# KGGR_M2_MOS.net
KiCad netlist of a schematic drawn in EAGLE
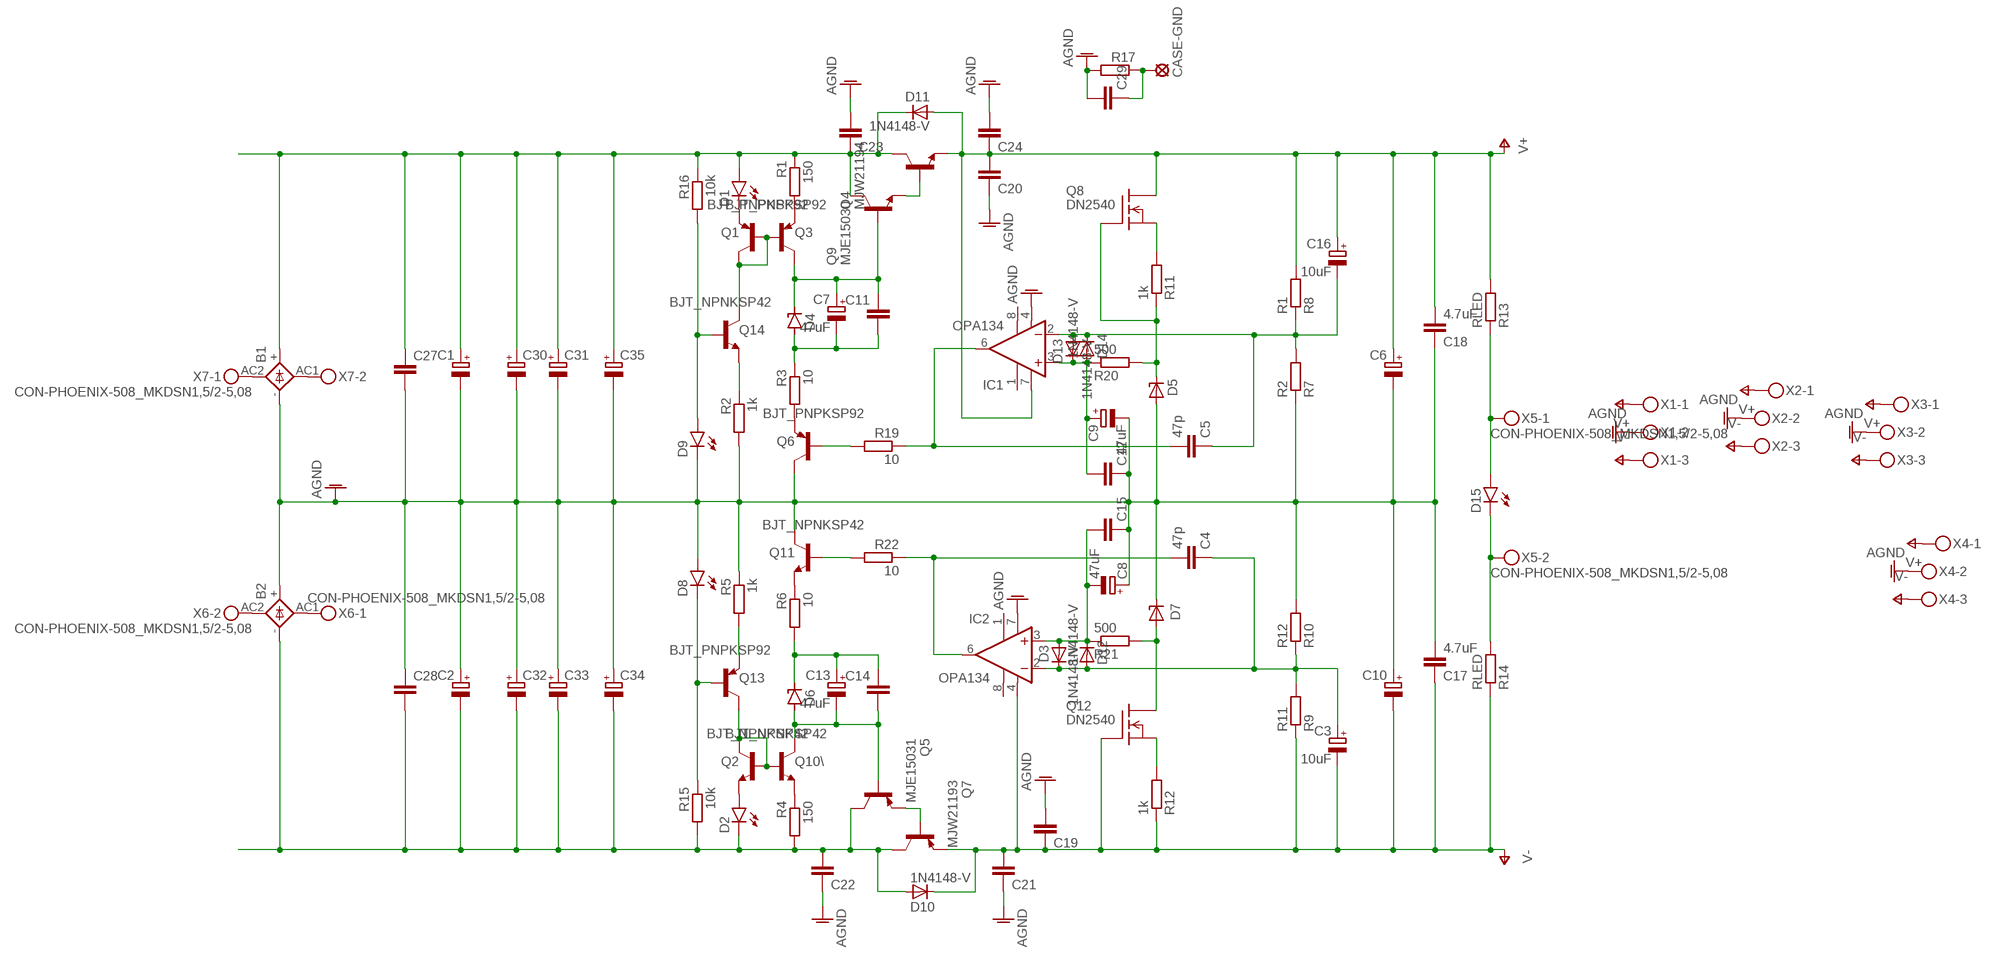
[diagram p0: schematic, sheet 1]

(export (version "E")
  (design (tool "Eeschema 10.0.6"))
  (components
    (comp (ref "B1")
      (value "GBU4")
      (footprint "eagle-import:GBU4S")
      (libsource (lib "eagle-import") (part "GBU4"))
    )
    (comp (ref "B2")
      (value "GBU4")
      (footprint "eagle-import:GBU4S")
      (libsource (lib "eagle-import") (part "GBU4"))
    )
    (comp (ref "C1")
      (value "CPOL-EUE10-35")
      (footprint "eagle-import:EB35D")
      (libsource (lib "eagle-import") (part "CPOL-EUE10-35"))
    )
    (comp (ref "C2")
      (value "CPOL-EUE10-35")
      (footprint "eagle-import:EB35D")
      (libsource (lib "eagle-import") (part "CPOL-EUE10-35"))
    )
    (comp (ref "C3")
      (value "10uF")
      (footprint "eagle-import:E5-8,5")
      (libsource (lib "eagle-import") (part "CPOL-EUE5-8.5"))
    )
    (comp (ref "C4")
      (value "47p")
      (footprint "eagle-import:C025_050-025X075")
      (libsource (lib "eagle-import") (part "C-EU025_050-025X075"))
    )
    (comp (ref "C5")
      (value "47p")
      (footprint "eagle-import:C025_050-025X075")
      (libsource (lib "eagle-import") (part "C-EU025_050-025X075"))
    )
    (comp (ref "C6")
      (value "CPOL-EUE7.5-18")
      (footprint "eagle-import:E7,5-18")
      (libsource (lib "eagle-import") (part "CPOL-EUE7.5-18"))
    )
    (comp (ref "C7")
      (value "47uF")
      (footprint "eagle-import:E5-8,5")
      (libsource (lib "eagle-import") (part "CPOL-EUE5-8.5"))
    )
    (comp (ref "C8")
      (value "47uF")
      (footprint "eagle-import:E5-8,5")
      (libsource (lib "eagle-import") (part "CPOL-EUE5-8.5"))
    )
    (comp (ref "C9")
      (value "47uF")
      (footprint "eagle-import:E5-8,5")
      (libsource (lib "eagle-import") (part "CPOL-EUE5-8.5"))
    )
    (comp (ref "C10")
      (value "CPOL-EUE7.5-18")
      (footprint "eagle-import:E7,5-18")
      (libsource (lib "eagle-import") (part "CPOL-EUE7.5-18"))
    )
    (comp (ref "C11")
      (value "C-EU050-035X075")
      (footprint "eagle-import:C050-035X075")
      (libsource (lib "eagle-import") (part "C-EU050-035X075"))
    )
    (comp (ref "C12")
      (value "C-EU050-035X075")
      (footprint "eagle-import:C050-035X075")
      (libsource (lib "eagle-import") (part "C-EU050-035X075"))
    )
    (comp (ref "C13")
      (value "47uF")
      (footprint "eagle-import:E5-8,5")
      (libsource (lib "eagle-import") (part "CPOL-EUE5-8.5"))
    )
    (comp (ref "C14")
      (value "C-EU050-035X075")
      (footprint "eagle-import:C050-035X075")
      (libsource (lib "eagle-import") (part "C-EU050-035X075"))
    )
    (comp (ref "C15")
      (value "C-EU050-035X075")
      (footprint "eagle-import:C050-035X075")
      (libsource (lib "eagle-import") (part "C-EU050-035X075"))
    )
    (comp (ref "C16")
      (value "10uF")
      (footprint "eagle-import:E5-8,5")
      (libsource (lib "eagle-import") (part "CPOL-EUE5-8.5"))
    )
    (comp (ref "C17")
      (value "4.7uF")
      (footprint "eagle-import:C050-075X075")
      (libsource (lib "eagle-import") (part "C-EU050-075X075"))
    )
    (comp (ref "C18")
      (value "4.7uF")
      (footprint "eagle-import:C050-075X075")
      (libsource (lib "eagle-import") (part "C-EU050-075X075"))
    )
    (comp (ref "C19")
      (value "C-EU050-035X075")
      (footprint "eagle-import:C050-035X075")
      (libsource (lib "eagle-import") (part "C-EU050-035X075"))
    )
    (comp (ref "C20")
      (value "C-EU050-035X075")
      (footprint "eagle-import:C050-035X075")
      (libsource (lib "eagle-import") (part "C-EU050-035X075"))
    )
    (comp (ref "C21")
      (value "C-EU050-035X075")
      (footprint "eagle-import:C050-035X075")
      (libsource (lib "eagle-import") (part "C-EU050-035X075"))
    )
    (comp (ref "C22")
      (value "C-EU050-075X075")
      (footprint "eagle-import:C050-075X075")
      (libsource (lib "eagle-import") (part "C-EU050-075X075"))
    )
    (comp (ref "C23")
      (value "C-EU050-075X075")
      (footprint "eagle-import:C050-075X075")
      (libsource (lib "eagle-import") (part "C-EU050-075X075"))
    )
    (comp (ref "C24")
      (value "C-EU050-035X075")
      (footprint "eagle-import:C050-035X075")
      (libsource (lib "eagle-import") (part "C-EU050-035X075"))
    )
    (comp (ref "C27")
      (value "C-EU102_152-062X184")
      (footprint "eagle-import:C102_152-062X184")
      (libsource (lib "eagle-import") (part "C-EU102_152-062X184"))
    )
    (comp (ref "C28")
      (value "C-EU102_152-062X184")
      (footprint "eagle-import:C102_152-062X184")
      (libsource (lib "eagle-import") (part "C-EU102_152-062X184"))
    )
    (comp (ref "C29")
      (value "C-EU102_152-062X184")
      (footprint "eagle-import:C102_152-062X184")
      (libsource (lib "eagle-import") (part "C-EU102_152-062X184"))
    )
    (comp (ref "C30")
      (value "CPOL-EUE7.5-18")
      (footprint "eagle-import:E7,5-18")
      (libsource (lib "eagle-import") (part "CPOL-EUE7.5-18"))
    )
    (comp (ref "C31")
      (value "CPOL-EUE7.5-18")
      (footprint "eagle-import:E7,5-18")
      (libsource (lib "eagle-import") (part "CPOL-EUE7.5-18"))
    )
    (comp (ref "C32")
      (value "CPOL-EUE7.5-18")
      (footprint "eagle-import:E7,5-18")
      (libsource (lib "eagle-import") (part "CPOL-EUE7.5-18"))
    )
    (comp (ref "C33")
      (value "CPOL-EUE7.5-18")
      (footprint "eagle-import:E7,5-18")
      (libsource (lib "eagle-import") (part "CPOL-EUE7.5-18"))
    )
    (comp (ref "C34")
      (value "CPOL-EUE7.5-18")
      (footprint "eagle-import:E7,5-18")
      (libsource (lib "eagle-import") (part "CPOL-EUE7.5-18"))
    )
    (comp (ref "C35")
      (value "CPOL-EUE7.5-18")
      (footprint "eagle-import:E7,5-18")
      (libsource (lib "eagle-import") (part "CPOL-EUE7.5-18"))
    )
    (comp (ref "CASE-GND")
      (value "SE14")
      (footprint "eagle-import:SE14")
      (libsource (lib "eagle-import") (part "SE14"))
    )
    (comp (ref "D1")
      (value "LED5MM")
      (footprint "eagle-import:LED5MM")
      (libsource (lib "eagle-import") (part "LED5MM"))
    )
    (comp (ref "D2")
      (value "LED5MM")
      (footprint "eagle-import:LED5MM")
      (libsource (lib "eagle-import") (part "LED5MM"))
    )
    (comp (ref "D3")
      (value "1N4148-V")
      (footprint "eagle-import:1N4148")
      (libsource (lib "eagle-import") (part "1N4148-V"))
    )
    (comp (ref "D4")
      (value "1N4728")
      (footprint "eagle-import:DO41Z10")
      (libsource (lib "eagle-import") (part "1N4728"))
    )
    (comp (ref "D5")
      (value "LT1021")
      (footprint "eagle-import:DIL08")
      (libsource (lib "eagle-import") (part "LT1021-V"))
    )
    (comp (ref "D6")
      (value "1N4728")
      (footprint "eagle-import:DO41Z10")
      (libsource (lib "eagle-import") (part "1N4728"))
    )
    (comp (ref "D7")
      (value "LT1021")
      (footprint "eagle-import:DIL08")
      (libsource (lib "eagle-import") (part "LT1021-V"))
    )
    (comp (ref "D8")
      (value "LED5MM")
      (footprint "eagle-import:LED5MM")
      (libsource (lib "eagle-import") (part "LED5MM"))
    )
    (comp (ref "D9")
      (value "LED5MM")
      (footprint "eagle-import:LED5MM")
      (libsource (lib "eagle-import") (part "LED5MM"))
    )
    (comp (ref "D10")
      (value "1N4148-V")
      (footprint "eagle-import:1N4148")
      (libsource (lib "eagle-import") (part "1N4148-V"))
    )
    (comp (ref "D11")
      (value "1N4148-V")
      (footprint "eagle-import:1N4148")
      (libsource (lib "eagle-import") (part "1N4148-V"))
    )
    (comp (ref "D12")
      (value "1N4148-V")
      (footprint "eagle-import:1N4148")
      (libsource (lib "eagle-import") (part "1N4148-V"))
    )
    (comp (ref "D13")
      (value "1N4148-V")
      (footprint "eagle-import:1N4148")
      (libsource (lib "eagle-import") (part "1N4148-V"))
    )
    (comp (ref "D14")
      (value "1N4148-V")
      (footprint "eagle-import:1N4148")
      (libsource (lib "eagle-import") (part "1N4148-V"))
    )
    (comp (ref "D15")
      (value "LED5MM")
      (footprint "eagle-import:LED5MM")
      (libsource (lib "eagle-import") (part "LED5MM"))
    )
    (comp (ref "IC1")
      (value "OPA134")
      (footprint "eagle-import:DIL08")
      (fields (field (name "MF") "TEXAS INSTRUMENTS") (field (name "MPN") "OPA134PA"))
      (libsource (lib "eagle-import") (part "OPA134P"))
    )
    (comp (ref "IC2")
      (value "OPA134")
      (footprint "eagle-import:DIL08")
      (fields (field (name "MF") "TEXAS INSTRUMENTS") (field (name "MPN") "OPA134PA"))
      (libsource (lib "eagle-import") (part "OPA134P"))
    )
    (comp (ref "Q1")
      (value "BJT_PNPKSP92")
      (footprint "eagle-import:TRANSISTOR_TO92-EBC_P")
      (libsource (lib "eagle-import") (part "BJT_PNPKSP92"))
    )
    (comp (ref "Q2")
      (value "BJT_NPNKSP42")
      (footprint "eagle-import:TRANSISTOR_TO92-EBC_N")
      (libsource (lib "eagle-import") (part "BJT_NPNKSP42"))
    )
    (comp (ref "Q3")
      (value "BJT_PNPKSP92")
      (footprint "eagle-import:TRANSISTOR_TO92-EBC_P")
      (libsource (lib "eagle-import") (part "BJT_PNPKSP92"))
    )
    (comp (ref "Q4")
      (value "MJW21194")
      (footprint "eagle-import:TRANSISTOR_TO247_BCE_N")
      (libsource (lib "eagle-import") (part "BJT_NPNMJL4281"))
    )
    (comp (ref "Q5")
      (value "MJE15031")
      (footprint "eagle-import:TO220KG")
      (libsource (lib "eagle-import") (part "MJE15031"))
    )
    (comp (ref "Q6")
      (value "BJT_PNPKSP92")
      (footprint "eagle-import:TRANSISTOR_TO92-EBC_P")
      (libsource (lib "eagle-import") (part "BJT_PNPKSP92"))
    )
    (comp (ref "Q7")
      (value "MJW21193")
      (footprint "eagle-import:TRANSISTOR_TO247_BCE_P")
      (libsource (lib "eagle-import") (part "BJT_PNPMJL4302"))
    )
    (comp (ref "Q8")
      (value "DN2540")
      (footprint "eagle-import:TO92-")
      (libsource (lib "eagle-import") (part "2N7000"))
    )
    (comp (ref "Q9")
      (value "MJE15030")
      (footprint "eagle-import:TO220KG")
      (libsource (lib "eagle-import") (part "MJE15030"))
    )
    (comp (ref "Q10\\")
      (value "BJT_NPNKSP42")
      (footprint "eagle-import:TRANSISTOR_TO92-EBC_N")
      (libsource (lib "eagle-import") (part "BJT_NPNKSP42"))
    )
    (comp (ref "Q11")
      (value "BJT_NPNKSP42")
      (footprint "eagle-import:TRANSISTOR_TO92-EBC_N")
      (libsource (lib "eagle-import") (part "BJT_NPNKSP42"))
    )
    (comp (ref "Q12")
      (value "DN2540")
      (footprint "eagle-import:TO92-")
      (libsource (lib "eagle-import") (part "2N7000"))
    )
    (comp (ref "Q13")
      (value "BJT_PNPKSP92")
      (footprint "eagle-import:TRANSISTOR_TO92-EBC_P")
      (libsource (lib "eagle-import") (part "BJT_PNPKSP92"))
    )
    (comp (ref "Q14")
      (value "BJT_NPNKSP42")
      (footprint "eagle-import:TRANSISTOR_TO92-EBC_N")
      (libsource (lib "eagle-import") (part "BJT_NPNKSP42"))
    )
    (comp (ref "R1")
      (value "150")
      (footprint "eagle-import:0309_12")
      (libsource (lib "eagle-import") (part "R-EU_0309/12"))
    )
    (comp (ref "R2")
      (value "1k")
      (footprint "eagle-import:0309_12")
      (libsource (lib "eagle-import") (part "R-EU_0309/12"))
    )
    (comp (ref "R3")
      (value "10")
      (footprint "eagle-import:0309_12")
      (libsource (lib "eagle-import") (part "R-EU_0309/12"))
    )
    (comp (ref "R4")
      (value "150")
      (footprint "eagle-import:0309_12")
      (libsource (lib "eagle-import") (part "R-EU_0309/12"))
    )
    (comp (ref "R5")
      (value "1k")
      (footprint "eagle-import:0309_12")
      (libsource (lib "eagle-import") (part "R-EU_0309/12"))
    )
    (comp (ref "R6")
      (value "10")
      (footprint "eagle-import:0309_12")
      (libsource (lib "eagle-import") (part "R-EU_0309/12"))
    )
    (comp (ref "R7")
      (value "R2")
      (footprint "eagle-import:0309_12")
      (libsource (lib "eagle-import") (part "R-EU_0309/12"))
    )
    (comp (ref "R8")
      (value "R1")
      (footprint "eagle-import:0309_12")
      (libsource (lib "eagle-import") (part "R-EU_0309/12"))
    )
    (comp (ref "R9")
      (value "R11")
      (footprint "eagle-import:0309_12")
      (libsource (lib "eagle-import") (part "R-EU_0309/12"))
    )
    (comp (ref "R10")
      (value "R12")
      (footprint "eagle-import:0309_12")
      (libsource (lib "eagle-import") (part "R-EU_0309/12"))
    )
    (comp (ref "R11")
      (value "1k")
      (footprint "eagle-import:0309_12")
      (libsource (lib "eagle-import") (part "R-EU_0309/12"))
    )
    (comp (ref "R12")
      (value "1k")
      (footprint "eagle-import:0309_12")
      (libsource (lib "eagle-import") (part "R-EU_0309/12"))
    )
    (comp (ref "R13")
      (value "RLED")
      (footprint "eagle-import:0309_12")
      (libsource (lib "eagle-import") (part "R-EU_0309/12"))
    )
    (comp (ref "R14")
      (value "RLED")
      (footprint "eagle-import:0309_12")
      (libsource (lib "eagle-import") (part "R-EU_0309/12"))
    )
    (comp (ref "R15")
      (value "10k")
      (footprint "eagle-import:0309_12")
      (libsource (lib "eagle-import") (part "R-EU_0309/12"))
    )
    (comp (ref "R16")
      (value "10k")
      (footprint "eagle-import:0309_12")
      (libsource (lib "eagle-import") (part "R-EU_0309/12"))
    )
    (comp (ref "R17")
      (value "R-EU_0617/22")
      (footprint "eagle-import:0617_22")
      (libsource (lib "eagle-import") (part "R-EU_0617/22"))
    )
    (comp (ref "R19")
      (value "10")
      (footprint "eagle-import:0309_12")
      (libsource (lib "eagle-import") (part "R-EU_0309/12"))
    )
    (comp (ref "R20")
      (value "500")
      (footprint "eagle-import:0309_12")
      (libsource (lib "eagle-import") (part "R-EU_0309/12"))
    )
    (comp (ref "R21")
      (value "500")
      (footprint "eagle-import:0309_12")
      (libsource (lib "eagle-import") (part "R-EU_0309/12"))
    )
    (comp (ref "R22")
      (value "10")
      (footprint "eagle-import:0309_12")
      (libsource (lib "eagle-import") (part "R-EU_0309/12"))
    )
    (comp (ref "X1")
      (value "CON-PHOENIX-508_MKDSN1,5/3-5,08")
      (footprint "eagle-import:CON-PHOENIX-508_MKDSN1,5_3-5,08")
      (libsource (lib "eagle-import") (part "CON-PHOENIX-508_MKDSN1,5/3-5,08"))
    )
    (comp (ref "X2")
      (value "CON-PHOENIX-508_MKDSN1,5/3-5,08")
      (footprint "eagle-import:CON-PHOENIX-508_MKDSN1,5_3-5,08")
      (libsource (lib "eagle-import") (part "CON-PHOENIX-508_MKDSN1,5/3-5,08"))
    )
    (comp (ref "X3")
      (value "CON-PHOENIX-508_MKDSN1,5/3-5,08")
      (footprint "eagle-import:CON-PHOENIX-508_MKDSN1,5_3-5,08")
      (libsource (lib "eagle-import") (part "CON-PHOENIX-508_MKDSN1,5/3-5,08"))
    )
    (comp (ref "X4")
      (value "CON-PHOENIX-508_MKDSN1,5/3-5,08")
      (footprint "eagle-import:CON-PHOENIX-508_MKDSN1,5_3-5,08")
      (libsource (lib "eagle-import") (part "CON-PHOENIX-508_MKDSN1,5/3-5,08"))
    )
    (comp (ref "X5")
      (value "CON-PHOENIX-508_MKDSN1,5/2-5,08")
      (footprint "eagle-import:CON-PHOENIX-508_MKDSN1,5_2-5,08")
      (libsource (lib "eagle-import") (part "CON-PHOENIX-508_MKDSN1,5/2-5,08"))
    )
    (comp (ref "X6")
      (value "CON-PHOENIX-508_MKDSN1,5/2-5,08")
      (footprint "eagle-import:CON-PHOENIX-508_MKDSN1,5_2-5,08")
      (libsource (lib "eagle-import") (part "CON-PHOENIX-508_MKDSN1,5/2-5,08"))
    )
    (comp (ref "X7")
      (value "CON-PHOENIX-508_MKDSN1,5/2-5,08")
      (footprint "eagle-import:CON-PHOENIX-508_MKDSN1,5_2-5,08")
      (libsource (lib "eagle-import") (part "CON-PHOENIX-508_MKDSN1,5/2-5,08"))
    )
  )
  (nets
    (net (code "1") (name "AGND") (class "Default")
      (node (ref "B1") (pin "-") (pinfunction "-_-") (pintype "passive"))
      (node (ref "B2") (pin "+") (pinfunction "+_+") (pintype "passive"))
      (node (ref "C1") (pin "-") (pinfunction "-_-") (pintype "passive"))
      (node (ref "C10") (pin "+") (pinfunction "+_+") (pintype "passive"))
      (node (ref "C12") (pin "1") (pinfunction "1_1") (pintype "passive"))
      (node (ref "C15") (pin "1") (pinfunction "1_1") (pintype "passive"))
      (node (ref "C17") (pin "2") (pinfunction "2_2") (pintype "passive"))
      (node (ref "C18") (pin "1") (pinfunction "1_1") (pintype "passive"))
      (node (ref "C19") (pin "2") (pinfunction "2_2") (pintype "passive"))
      (node (ref "C2") (pin "+") (pinfunction "+_+") (pintype "passive"))
      (node (ref "C20") (pin "1") (pinfunction "1_1") (pintype "passive"))
      (node (ref "C21") (pin "1") (pinfunction "1_1") (pintype "passive"))
      (node (ref "C22") (pin "1") (pinfunction "1_1") (pintype "passive"))
      (node (ref "C23") (pin "2") (pinfunction "2_2") (pintype "passive"))
      (node (ref "C24") (pin "2") (pinfunction "2_2") (pintype "passive"))
      (node (ref "C27") (pin "2") (pinfunction "2_2") (pintype "passive"))
      (node (ref "C27") (pin "3") (pinfunction "2_3") (pintype "passive"))
      (node (ref "C28") (pin "1") (pinfunction "1_1") (pintype "passive"))
      (node (ref "C29") (pin "2") (pinfunction "2_2") (pintype "passive"))
      (node (ref "C29") (pin "3") (pinfunction "2_3") (pintype "passive"))
      (node (ref "C30") (pin "-") (pinfunction "-_-") (pintype "passive"))
      (node (ref "C31") (pin "-") (pinfunction "-_-") (pintype "passive"))
      (node (ref "C32") (pin "+") (pinfunction "+_+") (pintype "passive"))
      (node (ref "C33") (pin "+") (pinfunction "+_+") (pintype "passive"))
      (node (ref "C34") (pin "+") (pinfunction "+_+") (pintype "passive"))
      (node (ref "C35") (pin "-") (pinfunction "-_-") (pintype "passive"))
      (node (ref "C6") (pin "-") (pinfunction "-_-") (pintype "passive"))
      (node (ref "C8") (pin "+") (pinfunction "+_+") (pintype "passive"))
      (node (ref "C9") (pin "-") (pinfunction "-_-") (pintype "passive"))
      (node (ref "D5") (pin "4") (pinfunction "GND_4") (pintype "passive"))
      (node (ref "D7") (pin "6") (pinfunction "OUT_6") (pintype "passive"))
      (node (ref "D8") (pin "A") (pinfunction "A_A") (pintype "passive"))
      (node (ref "D9") (pin "K") (pinfunction "C_K") (pintype "passive"))
      (node (ref "IC1") (pin "4") (pinfunction "V-_4") (pintype "power_in"))
      (node (ref "IC2") (pin "7") (pinfunction "V+_7") (pintype "power_in"))
      (node (ref "Q11") (pin "C") (pinfunction "C_C") (pintype "passive"))
      (node (ref "Q6") (pin "C") (pinfunction "C_C") (pintype "passive"))
      (node (ref "R10") (pin "2") (pinfunction "2_2") (pintype "passive"))
      (node (ref "R17") (pin "2") (pinfunction "2_2") (pintype "passive"))
      (node (ref "R2") (pin "2") (pinfunction "2_2") (pintype "passive"))
      (node (ref "R5") (pin "1") (pinfunction "1_1") (pintype "passive"))
      (node (ref "R7") (pin "1") (pinfunction "1_1") (pintype "passive"))
      (node (ref "X1") (pin "2") (pinfunction "KL_2") (pintype "passive"))
      (node (ref "X2") (pin "2") (pinfunction "KL_2") (pintype "passive"))
      (node (ref "X3") (pin "2") (pinfunction "KL_2") (pintype "passive"))
      (node (ref "X4") (pin "2") (pinfunction "KL_2") (pintype "passive"))
    )
    (net (code "2") (name "Net-(B1-AC1)") (class "Default")
      (node (ref "B1") (pin "AC2") (pinfunction "AC1_AC2") (pintype "passive"))
      (node (ref "X7") (pin "1") (pinfunction "KL_1") (pintype "passive"))
    )
    (net (code "3") (name "Net-(B1-AC2)") (class "Default")
      (node (ref "B1") (pin "AC1") (pinfunction "AC2_AC1") (pintype "passive"))
      (node (ref "X7") (pin "2") (pinfunction "KL_2") (pintype "passive"))
    )
    (net (code "4") (name "Net-(B2-AC1)") (class "Default")
      (node (ref "B2") (pin "AC2") (pinfunction "AC1_AC2") (pintype "passive"))
      (node (ref "X6") (pin "2") (pinfunction "KL_2") (pintype "passive"))
    )
    (net (code "5") (name "Net-(B2-AC2)") (class "Default")
      (node (ref "B2") (pin "AC1") (pinfunction "AC2_AC1") (pintype "passive"))
      (node (ref "X6") (pin "1") (pinfunction "KL_1") (pintype "passive"))
    )
    (net (code "6") (name "Net-(C11-Pad2)") (class "Default")
      (node (ref "C11") (pin "2") (pinfunction "2_2") (pintype "passive"))
      (node (ref "C7") (pin "-") (pinfunction "-_-") (pintype "passive"))
      (node (ref "D4") (pin "A") (pinfunction "A_A") (pintype "passive"))
      (node (ref "R3") (pin "1") (pinfunction "1_1") (pintype "passive"))
    )
    (net (code "7") (name "Net-(C13-Pad+)") (class "Default")
      (node (ref "C13") (pin "+") (pinfunction "+_+") (pintype "passive"))
      (node (ref "C14") (pin "1") (pinfunction "1_1") (pintype "passive"))
      (node (ref "D6") (pin "C") (pinfunction "C_C") (pintype "passive"))
      (node (ref "R6") (pin "2") (pinfunction "2_2") (pintype "passive"))
    )
    (net (code "8") (name "Net-(C29-Pad1)") (class "Default")
      (node (ref "C29") (pin "1") (pinfunction "1_1") (pintype "passive"))
      (node (ref "CASE-GND") (pin "MP") (pinfunction "MP_MP") (pintype "passive"))
      (node (ref "R17") (pin "1") (pinfunction "1_1") (pintype "passive"))
    )
    (net (code "9") (name "Net-(D1-C)") (class "Default")
      (node (ref "D1") (pin "K") (pinfunction "C_K") (pintype "passive"))
      (node (ref "Q1") (pin "E") (pinfunction "E_E") (pintype "passive"))
    )
    (net (code "10") (name "Net-(D2-C)") (class "Default")
      (node (ref "B2") (pin "-") (pinfunction "-_-") (pintype "passive"))
      (node (ref "C2") (pin "-") (pinfunction "-_-") (pintype "passive"))
      (node (ref "C22") (pin "2") (pinfunction "2_2") (pintype "passive"))
      (node (ref "C28") (pin "2") (pinfunction "2_2") (pintype "passive"))
      (node (ref "C28") (pin "3") (pinfunction "2_3") (pintype "passive"))
      (node (ref "C32") (pin "-") (pinfunction "-_-") (pintype "passive"))
      (node (ref "C33") (pin "-") (pinfunction "-_-") (pintype "passive"))
      (node (ref "C34") (pin "-") (pinfunction "-_-") (pintype "passive"))
      (node (ref "D10") (pin "A") (pinfunction "A_A") (pintype "passive"))
      (node (ref "D2") (pin "K") (pinfunction "C_K") (pintype "passive"))
      (node (ref "Q5") (pin "2") (pinfunction "C_2") (pintype "passive"))
      (node (ref "Q7") (pin "C") (pinfunction "C_C") (pintype "passive"))
      (node (ref "R15") (pin "2") (pinfunction "2_2") (pintype "passive"))
      (node (ref "R4") (pin "2") (pinfunction "2_2") (pintype "passive"))
    )
    (net (code "11") (name "Net-(D2-PadA)") (class "Default")
      (node (ref "D2") (pin "A") (pinfunction "A_A") (pintype "passive"))
      (node (ref "Q2") (pin "E") (pinfunction "E_E") (pintype "passive"))
    )
    (net (code "12") (name "Net-(D5-OUT)") (class "Default")
      (node (ref "D5") (pin "6") (pinfunction "OUT_6") (pintype "passive"))
      (node (ref "Q8") (pin "2") (pinfunction "G_2") (pintype "passive"))
      (node (ref "R11") (pin "1") (pinfunction "1_1") (pintype "passive"))
      (node (ref "R20") (pin "2") (pinfunction "2_2") (pintype "passive"))
    )
    (net (code "13") (name "Net-(D7-GND)") (class "Default")
      (node (ref "D7") (pin "4") (pinfunction "GND_4") (pintype "passive"))
      (node (ref "Q12") (pin "1") (pinfunction "D_1") (pintype "passive"))
      (node (ref "R21") (pin "2") (pinfunction "2_2") (pintype "passive"))
    )
    (net (code "14") (name "Net-(D8-C)") (class "Default")
      (node (ref "D8") (pin "K") (pinfunction "C_K") (pintype "passive"))
      (node (ref "Q13") (pin "B") (pinfunction "B_B") (pintype "passive"))
      (node (ref "R15") (pin "1") (pinfunction "1_1") (pintype "passive"))
    )
    (net (code "15") (name "Net-(D9-PadA)") (class "Default")
      (node (ref "D9") (pin "A") (pinfunction "A_A") (pintype "passive"))
      (node (ref "Q14") (pin "B") (pinfunction "B_B") (pintype "passive"))
      (node (ref "R16") (pin "2") (pinfunction "2_2") (pintype "passive"))
    )
    (net (code "16") (name "Net-(D15-C)") (class "Default")
      (node (ref "D15") (pin "K") (pinfunction "C_K") (pintype "passive"))
      (node (ref "R14") (pin "2") (pinfunction "2_2") (pintype "passive"))
      (node (ref "X5") (pin "2") (pinfunction "KL_2") (pintype "passive"))
    )
    (net (code "17") (name "Net-(IC1-+IN)") (class "Default")
      (node (ref "C12") (pin "2") (pinfunction "2_2") (pintype "passive"))
      (node (ref "C9") (pin "+") (pinfunction "+_+") (pintype "passive"))
      (node (ref "D13") (pin "C") (pinfunction "C_C") (pintype "passive"))
      (node (ref "D14") (pin "A") (pinfunction "A_A") (pintype "passive"))
      (node (ref "IC1") (pin "3") (pinfunction "+IN_3") (pintype "input"))
      (node (ref "R20") (pin "1") (pinfunction "1_1") (pintype "passive"))
    )
    (net (code "18") (name "Net-(IC1--IN)") (class "Default")
      (node (ref "C16") (pin "-") (pinfunction "-_-") (pintype "passive"))
      (node (ref "C5") (pin "1") (pinfunction "1_1") (pintype "passive"))
      (node (ref "D13") (pin "A") (pinfunction "A_A") (pintype "passive"))
      (node (ref "D14") (pin "C") (pinfunction "C_C") (pintype "passive"))
      (node (ref "IC1") (pin "2") (pinfunction "-IN_2") (pintype "input"))
      (node (ref "R7") (pin "2") (pinfunction "2_2") (pintype "passive"))
      (node (ref "R8") (pin "1") (pinfunction "1_1") (pintype "passive"))
    )
    (net (code "19") (name "Net-(IC1-OUT)") (class "Default")
      (node (ref "C5") (pin "2") (pinfunction "2_2") (pintype "passive"))
      (node (ref "C5") (pin "3") (pinfunction "2_3") (pintype "passive"))
      (node (ref "IC1") (pin "6") (pinfunction "OUT_6") (pintype "output"))
      (node (ref "R19") (pin "1") (pinfunction "1_1") (pintype "passive"))
    )
    (net (code "20") (name "Net-(IC2-+IN)") (class "Default")
      (node (ref "C15") (pin "2") (pinfunction "2_2") (pintype "passive"))
      (node (ref "C8") (pin "-") (pinfunction "-_-") (pintype "passive"))
      (node (ref "D12") (pin "C") (pinfunction "C_C") (pintype "passive"))
      (node (ref "D3") (pin "A") (pinfunction "A_A") (pintype "passive"))
      (node (ref "IC2") (pin "3") (pinfunction "+IN_3") (pintype "input"))
      (node (ref "R21") (pin "1") (pinfunction "1_1") (pintype "passive"))
    )
    (net (code "21") (name "Net-(IC2--IN)") (class "Default")
      (node (ref "C3") (pin "+") (pinfunction "+_+") (pintype "passive"))
      (node (ref "C4") (pin "1") (pinfunction "1_1") (pintype "passive"))
      (node (ref "D12") (pin "A") (pinfunction "A_A") (pintype "passive"))
      (node (ref "D3") (pin "C") (pinfunction "C_C") (pintype "passive"))
      (node (ref "IC2") (pin "2") (pinfunction "-IN_2") (pintype "input"))
      (node (ref "R10") (pin "1") (pinfunction "1_1") (pintype "passive"))
      (node (ref "R9") (pin "2") (pinfunction "2_2") (pintype "passive"))
    )
    (net (code "22") (name "Net-(IC2-OUT)") (class "Default")
      (node (ref "C4") (pin "2") (pinfunction "2_2") (pintype "passive"))
      (node (ref "C4") (pin "3") (pinfunction "2_3") (pintype "passive"))
      (node (ref "IC2") (pin "6") (pinfunction "OUT_6") (pintype "output"))
      (node (ref "R22") (pin "1") (pinfunction "1_1") (pintype "passive"))
    )
    (net (code "23") (name "Net-(Q1-PadB)") (class "Default")
      (node (ref "Q1") (pin "B") (pinfunction "B_B") (pintype "passive"))
      (node (ref "Q1") (pin "C") (pinfunction "C_C") (pintype "passive"))
      (node (ref "Q14") (pin "C") (pinfunction "C_C") (pintype "passive"))
      (node (ref "Q3") (pin "B") (pinfunction "B_B") (pintype "passive"))
    )
    (net (code "24") (name "Net-(Q3-PadE)") (class "Default")
      (node (ref "Q3") (pin "E") (pinfunction "E_E") (pintype "passive"))
      (node (ref "R1") (pin "2") (pinfunction "2_2") (pintype "passive"))
    )
    (net (code "25") (name "Net-(Q5-B)") (class "Default")
      (node (ref "C13") (pin "-") (pinfunction "-_-") (pintype "passive"))
      (node (ref "C14") (pin "2") (pinfunction "2_2") (pintype "passive"))
      (node (ref "D6") (pin "A") (pinfunction "A_A") (pintype "passive"))
      (node (ref "Q10\\") (pin "C") (pinfunction "C_C") (pintype "passive"))
      (node (ref "Q5") (pin "1") (pinfunction "B_1") (pintype "passive"))
    )
    (net (code "26") (name "Net-(Q5-E)") (class "Default")
      (node (ref "Q5") (pin "3") (pinfunction "E_3") (pintype "passive"))
      (node (ref "Q7") (pin "B") (pinfunction "B_B") (pintype "passive"))
    )
    (net (code "27") (name "Net-(Q6-PadB)") (class "Default")
      (node (ref "Q6") (pin "B") (pinfunction "B_B") (pintype "passive"))
      (node (ref "R19") (pin "2") (pinfunction "2_2") (pintype "passive"))
    )
    (net (code "28") (name "Net-(Q6-PadE)") (class "Default")
      (node (ref "Q6") (pin "E") (pinfunction "E_E") (pintype "passive"))
      (node (ref "R3") (pin "2") (pinfunction "2_2") (pintype "passive"))
    )
    (net (code "29") (name "Net-(Q8-S)") (class "Default")
      (node (ref "Q8") (pin "3") (pinfunction "S_3") (pintype "passive"))
      (node (ref "R11") (pin "2") (pinfunction "2_2") (pintype "passive"))
    )
    (net (code "30") (name "Net-(Q9-B)") (class "Default")
      (node (ref "C11") (pin "1") (pinfunction "1_1") (pintype "passive"))
      (node (ref "C7") (pin "+") (pinfunction "+_+") (pintype "passive"))
      (node (ref "D4") (pin "C") (pinfunction "C_C") (pintype "passive"))
      (node (ref "Q3") (pin "C") (pinfunction "C_C") (pintype "passive"))
      (node (ref "Q9") (pin "1") (pinfunction "B_1") (pintype "passive"))
    )
    (net (code "31") (name "Net-(Q9-C)") (class "Default")
      (node (ref "B1") (pin "+") (pinfunction "+_+") (pintype "passive"))
      (node (ref "C1") (pin "+") (pinfunction "+_+") (pintype "passive"))
      (node (ref "C23") (pin "1") (pinfunction "1_1") (pintype "passive"))
      (node (ref "C27") (pin "1") (pinfunction "1_1") (pintype "passive"))
      (node (ref "C30") (pin "+") (pinfunction "+_+") (pintype "passive"))
      (node (ref "C31") (pin "+") (pinfunction "+_+") (pintype "passive"))
      (node (ref "C35") (pin "+") (pinfunction "+_+") (pintype "passive"))
      (node (ref "D1") (pin "A") (pinfunction "A_A") (pintype "passive"))
      (node (ref "D11") (pin "C") (pinfunction "C_C") (pintype "passive"))
      (node (ref "Q4") (pin "C") (pinfunction "C_C") (pintype "passive"))
      (node (ref "Q9") (pin "2") (pinfunction "C_2") (pintype "passive"))
      (node (ref "R1") (pin "1") (pinfunction "1_1") (pintype "passive"))
      (node (ref "R16") (pin "1") (pinfunction "1_1") (pintype "passive"))
    )
    (net (code "32") (name "Net-(Q9-E)") (class "Default")
      (node (ref "Q4") (pin "B") (pinfunction "B_B") (pintype "passive"))
      (node (ref "Q9") (pin "3") (pinfunction "E_3") (pintype "passive"))
    )
    (net (code "33") (name "Net-(Q10\\-PadB)") (class "Default")
      (node (ref "Q10\\") (pin "B") (pinfunction "B_B") (pintype "passive"))
      (node (ref "Q13") (pin "C") (pinfunction "C_C") (pintype "passive"))
      (node (ref "Q2") (pin "B") (pinfunction "B_B") (pintype "passive"))
      (node (ref "Q2") (pin "C") (pinfunction "C_C") (pintype "passive"))
    )
    (net (code "34") (name "Net-(Q10\\-PadE)") (class "Default")
      (node (ref "Q10\\") (pin "E") (pinfunction "E_E") (pintype "passive"))
      (node (ref "R4") (pin "1") (pinfunction "1_1") (pintype "passive"))
    )
    (net (code "35") (name "Net-(Q11-PadB)") (class "Default")
      (node (ref "Q11") (pin "B") (pinfunction "B_B") (pintype "passive"))
      (node (ref "R22") (pin "2") (pinfunction "2_2") (pintype "passive"))
    )
    (net (code "36") (name "Net-(Q11-PadE)") (class "Default")
      (node (ref "Q11") (pin "E") (pinfunction "E_E") (pintype "passive"))
      (node (ref "R6") (pin "1") (pinfunction "1_1") (pintype "passive"))
    )
    (net (code "37") (name "Net-(Q12-S)") (class "Default")
      (node (ref "Q12") (pin "3") (pinfunction "S_3") (pintype "passive"))
      (node (ref "R12") (pin "2") (pinfunction "2_2") (pintype "passive"))
    )
    (net (code "38") (name "Net-(Q13-PadE)") (class "Default")
      (node (ref "Q13") (pin "E") (pinfunction "E_E") (pintype "passive"))
      (node (ref "R5") (pin "2") (pinfunction "2_2") (pintype "passive"))
    )
    (net (code "39") (name "Net-(Q14-PadE)") (class "Default")
      (node (ref "Q14") (pin "E") (pinfunction "E_E") (pintype "passive"))
      (node (ref "R2") (pin "1") (pinfunction "1_1") (pintype "passive"))
    )
    (net (code "40") (name "Net-(X5A-KL)") (class "Default")
      (node (ref "D15") (pin "A") (pinfunction "A_A") (pintype "passive"))
      (node (ref "R13") (pin "1") (pinfunction "1_1") (pintype "passive"))
      (node (ref "X5") (pin "1") (pinfunction "KL_1") (pintype "passive"))
    )
    (net (code "41") (name "V+") (class "Default")
      (node (ref "C16") (pin "+") (pinfunction "+_+") (pintype "passive"))
      (node (ref "C18") (pin "2") (pinfunction "2_2") (pintype "passive"))
      (node (ref "C20") (pin "2") (pinfunction "2_2") (pintype "passive"))
      (node (ref "C24") (pin "1") (pinfunction "1_1") (pintype "passive"))
      (node (ref "C6") (pin "+") (pinfunction "+_+") (pintype "passive"))
      (node (ref "D11") (pin "A") (pinfunction "A_A") (pintype "passive"))
      (node (ref "IC1") (pin "7") (pinfunction "V+_7") (pintype "power_in"))
      (node (ref "Q4") (pin "E") (pinfunction "E_E") (pintype "passive"))
      (node (ref "Q8") (pin "1") (pinfunction "D_1") (pintype "passive"))
      (node (ref "R13") (pin "2") (pinfunction "2_2") (pintype "passive"))
      (node (ref "R8") (pin "2") (pinfunction "2_2") (pintype "passive"))
      (node (ref "X1") (pin "1") (pinfunction "KL_1") (pintype "passive"))
      (node (ref "X2") (pin "1") (pinfunction "KL_1") (pintype "passive"))
      (node (ref "X3") (pin "1") (pinfunction "KL_1") (pintype "passive"))
      (node (ref "X4") (pin "1") (pinfunction "KL_1") (pintype "passive"))
    )
    (net (code "42") (name "V-") (class "Default")
      (node (ref "C10") (pin "-") (pinfunction "-_-") (pintype "passive"))
      (node (ref "C17") (pin "1") (pinfunction "1_1") (pintype "passive"))
      (node (ref "C19") (pin "1") (pinfunction "1_1") (pintype "passive"))
      (node (ref "C21") (pin "2") (pinfunction "2_2") (pintype "passive"))
      (node (ref "C3") (pin "-") (pinfunction "-_-") (pintype "passive"))
      (node (ref "D10") (pin "C") (pinfunction "C_C") (pintype "passive"))
      (node (ref "IC2") (pin "4") (pinfunction "V-_4") (pintype "power_in"))
      (node (ref "Q12") (pin "2") (pinfunction "G_2") (pintype "passive"))
      (node (ref "Q7") (pin "E") (pinfunction "E_E") (pintype "passive"))
      (node (ref "R12") (pin "1") (pinfunction "1_1") (pintype "passive"))
      (node (ref "R14") (pin "1") (pinfunction "1_1") (pintype "passive"))
      (node (ref "R9") (pin "1") (pinfunction "1_1") (pintype "passive"))
      (node (ref "X1") (pin "3") (pinfunction "KL_3") (pintype "passive"))
      (node (ref "X2") (pin "3") (pinfunction "KL_3") (pintype "passive"))
      (node (ref "X3") (pin "3") (pinfunction "KL_3") (pintype "passive"))
      (node (ref "X4") (pin "3") (pinfunction "KL_3") (pintype "passive"))
    )
    (net (code "43") (name "unconnected-(IC1-TRIM1-Pad1)") (class "Default")
      (node (ref "IC1") (pin "1") (pinfunction "TRIM1_1") (pintype "passive"))
    )
    (net (code "44") (name "unconnected-(IC1-TRIM2-Pad8)") (class "Default")
      (node (ref "IC1") (pin "8") (pinfunction "TRIM2_8") (pintype "passive"))
    )
    (net (code "45") (name "unconnected-(IC2-TRIM1-Pad1)") (class "Default")
      (node (ref "IC2") (pin "1") (pinfunction "TRIM1_1") (pintype "passive"))
    )
    (net (code "46") (name "unconnected-(IC2-TRIM2-Pad8)") (class "Default")
      (node (ref "IC2") (pin "8") (pinfunction "TRIM2_8") (pintype "passive"))
    )
  )
)
